# Input.net
KiCad netlist of a schematic drawn in Altium Designer
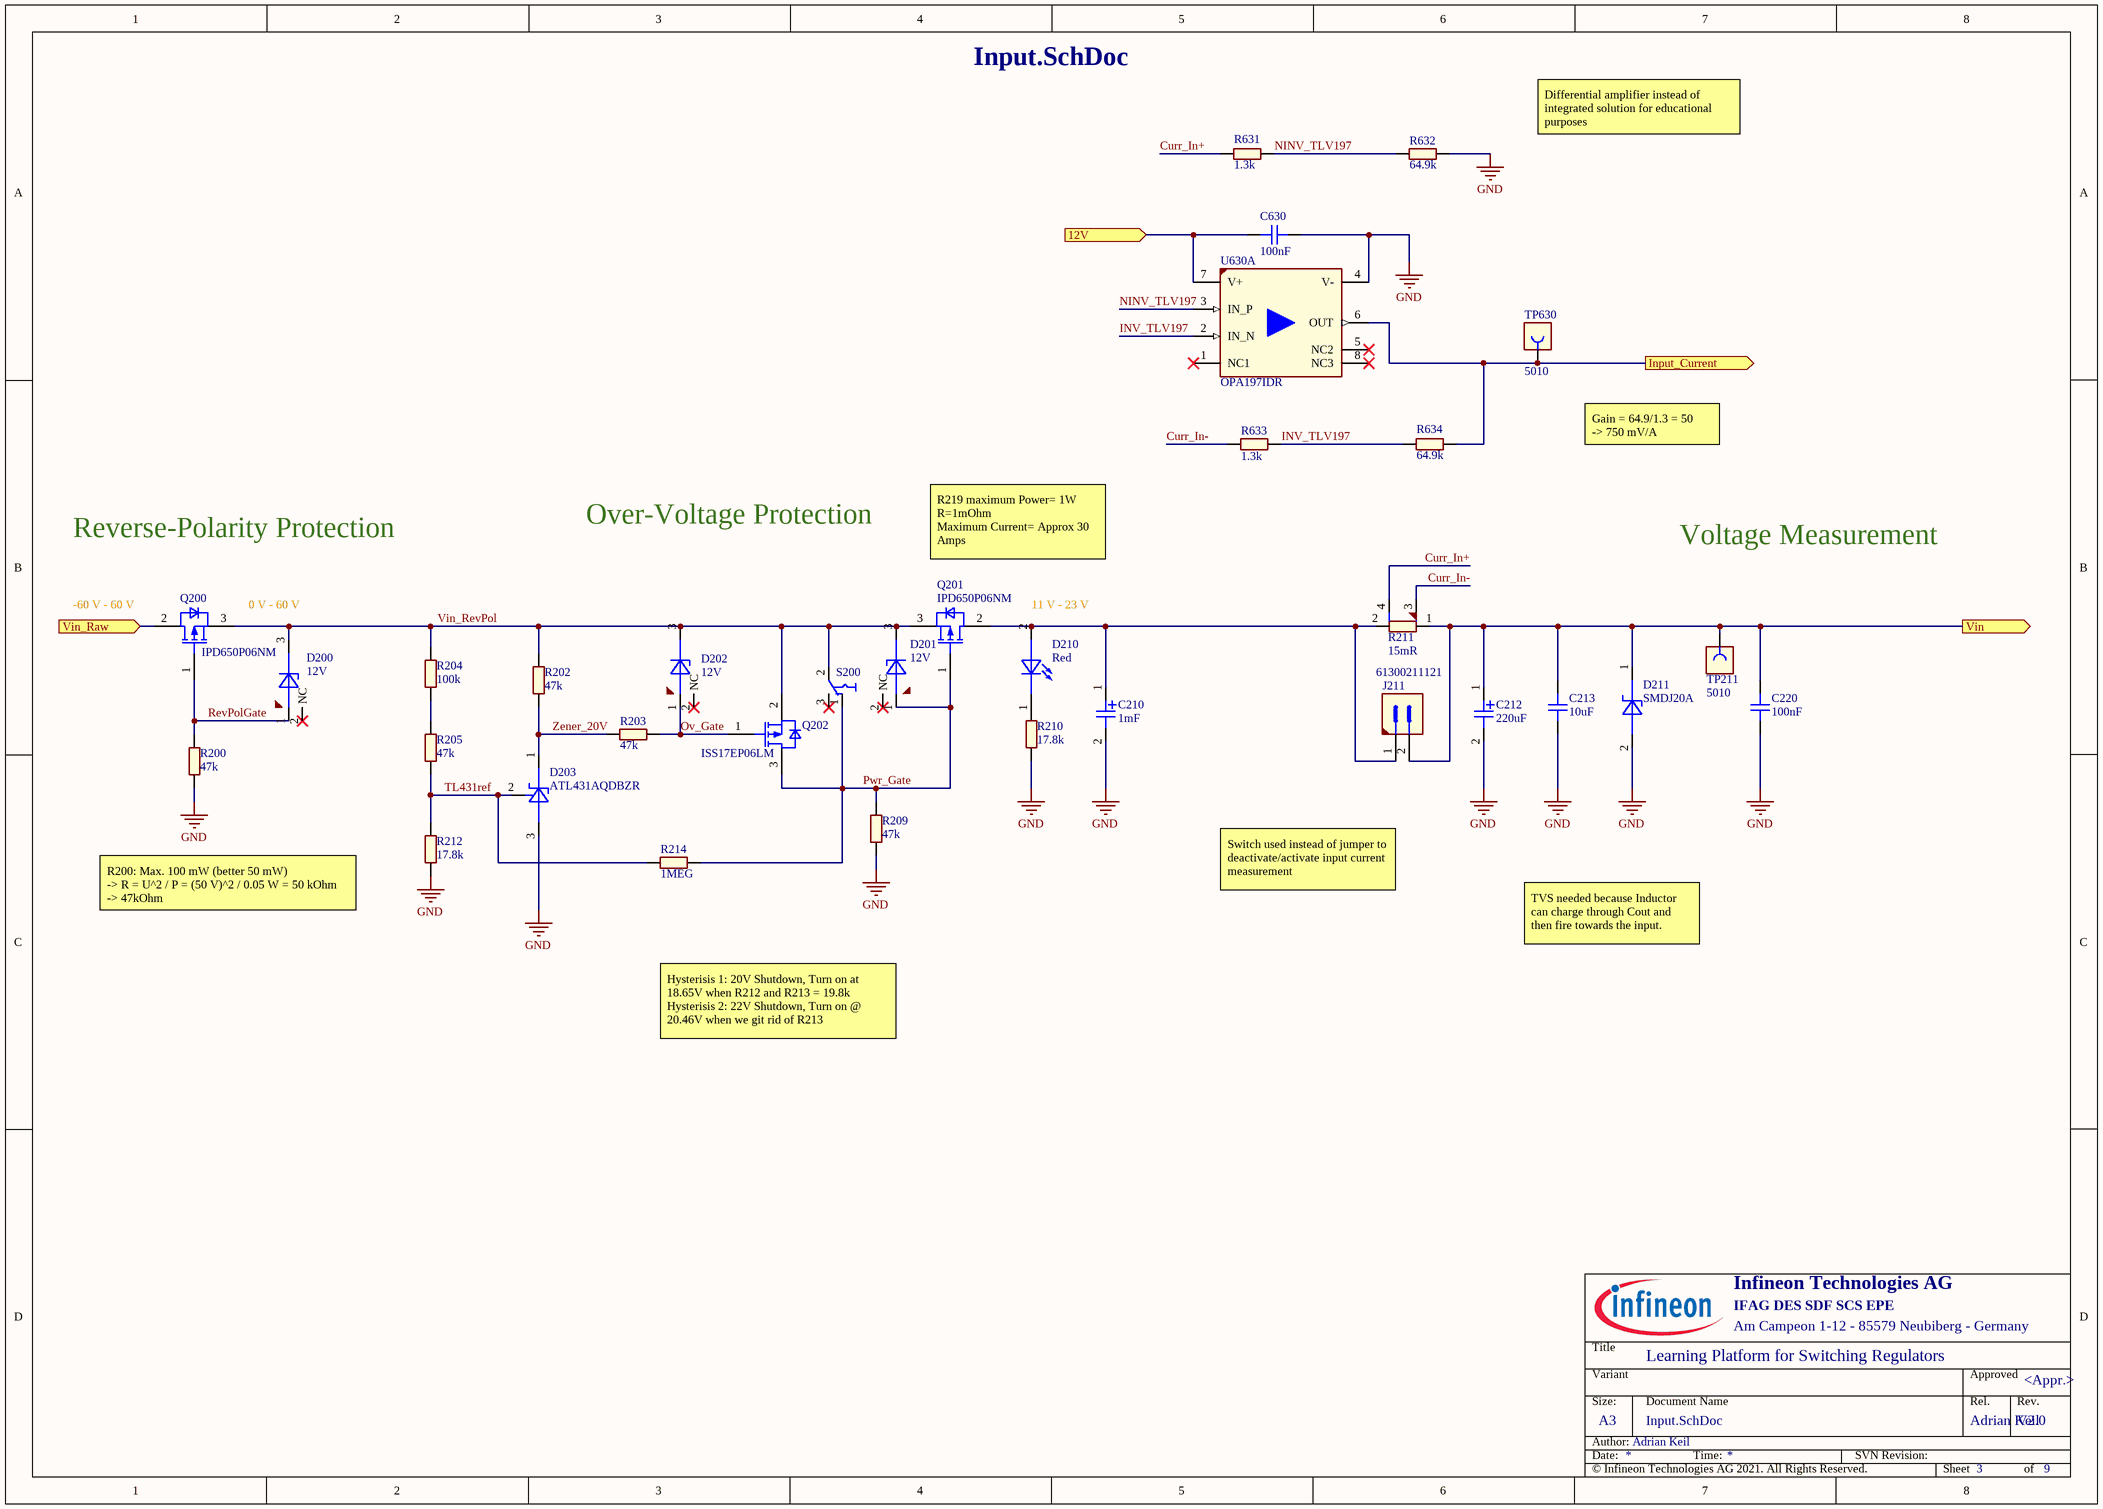
[diagram p0: Input.SchDoc]

(export (version "E")
  (design (tool "Eeschema 10.0.6"))
  (components
    (comp (ref "C210")
      (value "1mF")
      (footprint "CAPPRD500W60D1300H2700B")
      (fields (field (name "MANUFACTURER") "Kemet"))
      (libsource (lib "PCBLibraryData") (part "CAP-SGL-POL-02P_00000002"))
    )
    (comp (ref "C212")
      (value "220uF")
      (footprint "CAPAE1030X1050N-3")
      (fields (field (name "MANUFACTURER") "Nippon Chemi-Con"))
      (libsource (lib "PCBLibraryData") (part "CAP-SGL-POL-02P_00000002"))
    )
    (comp (ref "C213")
      (value "10uF")
      (footprint "CAPC3216X190N-1")
      (description "CAP / CERA / 10uF / 50V / 20% / X5R (EIA) / -55°C to 85°C / 1206 (3216) / SMD / -")
      (fields (field (name "MANUFACTURER") "Taiyo Yuden"))
      (libsource (lib "PCBLibraryData") (part "CAP-SGL-STD-02P_00000001"))
    )
    (comp (ref "C220")
      (value "100nF")
      (footprint "CAPC3216X125N-0")
      (description "CAP / CERA / 100nF / 50V / 10% / X7R (EIA) / -55°C to 125°C / 1206(3216) / SMD / -")
      (fields (field (name "LEGACY PARTNUMBER") "CAP01005660") (field (name "MANUFACTURER") "MuRata"))
      (libsource (lib "PCBLibraryData") (part "CAP-SGL-STD-02P_00000001"))
    )
    (comp (ref "C630")
      (value "100nF")
      (footprint "CAPC3216X125N-0")
      (description "CAP / CERA / 100nF / 50V / 10% / X7R (EIA) / -55°C to 125°C / 1206(3216) / SMD / -")
      (fields (field (name "LEGACY PARTNUMBER") "CAP01005660") (field (name "MANUFACTURER") "MuRata"))
      (libsource (lib "PCBLibraryData") (part "CAP-SGL-STD-02P_00000001"))
    )
    (comp (ref "D200")
      (value "12V")
      (footprint "SOT95P230X110-3N")
      (description "Voltage regulator diodes")
      (fields (field (name "MANUFACTURER") "Nexperia"))
      (libsource (lib "PCBLibraryData") (part "d_zener_a1c3_3p"))
    )
    (comp (ref "D201")
      (value "12V")
      (footprint "SOT95P230X110-3N")
      (description "Voltage regulator diodes")
      (fields (field (name "MANUFACTURER") "Nexperia"))
      (libsource (lib "PCBLibraryData") (part "d_zener_a1c3_3p"))
    )
    (comp (ref "D202")
      (value "12V")
      (footprint "SOT95P230X110-3N")
      (description "Voltage regulator diodes")
      (fields (field (name "MANUFACTURER") "Nexperia"))
      (libsource (lib "PCBLibraryData") (part "d_zener_a1c3_3p"))
    )
    (comp (ref "D203")
      (value "ATL431AQDBZR")
      (footprint "SOT95P237X112-3N-1")
      (description "ATL431 Adjustable Precision Shunt Regulator")
      (fields (field (name "MANUFACTURER") "Texas Instruments"))
      (libsource (lib "PCBLibraryData") (part "d_tvs_c1a3_3p"))
    )
    (comp (ref "D210")
      (value "Red")
      (footprint "LEDSC160X80X80-2N-1")
      (description "WL-SMCW SMT Mono-color Chip LED Waterclear, Red,630nm")
      (fields (field (name "MANUFACTURER") "Wurth Elektronik"))
      (libsource (lib "PCBLibraryData") (part "d_led_a"))
    )
    (comp (ref "D211")
      (value "SMDJ20A")
      (footprint "DIOM7959X262N")
      (description "TVS Diode, Low Profile Package, Built in Strain Relief, Glass Passivated Chip Junction")
      (fields (field (name "MANUFACTURER") "Littelfuse"))
      (libsource (lib "PCBLibraryData") (part "d_tvs_a"))
    )
    (comp (ref "J211")
      (value "61300211121")
      (footprint "CON-M-THT-61300211121")
      (description "Header, 2.54mm Pitch, 2 pin, Vertical, Single Row")
      (fields
        (field (name "LEGACY PARTNUMBER") "CON01500943")
        (field (name "MANUFACTURER") "Wurth Elektronik")
      )
      (libsource (lib "PCBLibraryData") (part "Header 2"))
    )
    (comp (ref "Q200")
      (value "IPD650P06NM")
      (footprint "TO228P998X250-3N-V2")
      (description "OptiMOS Power Transistor, -60 V")
      (fields (field (name "MANUFACTURER") "Infineon Technologies"))
      (libsource (lib "PCBLibraryData") (part "igfet_p_ch_enh_dio_1g2d3s_3p"))
    )
    (comp (ref "Q201")
      (value "IPD650P06NM")
      (footprint "TO228P998X250-3N-V2")
      (description "OptiMOS Power Transistor, -60 V")
      (fields (field (name "MANUFACTURER") "Infineon Technologies"))
      (libsource (lib "PCBLibraryData") (part "igfet_p_ch_enh_dio_1g2d3s_3p"))
    )
    (comp (ref "Q202")
      (value "ISS17EP06LM")
      (footprint "SOT95P240X110-3N-1-V")
      (description "OptiMOSTM Small Signal Transistor, -60 V")
      (fields (field (name "MANUFACTURER") "Infineon Technologies"))
      (libsource (lib "PCBLibraryData") (part "igfet_p_ch_enh_dio_1g2s3d_3p"))
    )
    (comp (ref "R200")
      (value "47k")
      (footprint "RESC3216X60N")
      (description "RES / STD / 47k / 250mW / 1% / 100ppm/K / -55°C to 155°C / 1206(3216) / SMD / -")
      (fields (field (name "LEGACY PARTNUMBER") "RES01802933") (field (name "MANUFACTURER") "Vishay"))
      (libsource (lib "") (part "RES-SGL-STD-02P_00000006_2"))
    )
    (comp (ref "R202")
      (value "47k")
      (footprint "RESC3216X60N")
      (description "RES / STD / 47k / 250mW / 1% / 100ppm/K / -55°C to 155°C / 1206(3216) / SMD / -")
      (fields (field (name "LEGACY PARTNUMBER") "RES01802933") (field (name "MANUFACTURER") "Vishay"))
      (libsource (lib "") (part "RES-SGL-STD-02P_00000006_2"))
    )
    (comp (ref "R203")
      (value "47k")
      (footprint "RESC3216X60N")
      (description "RES / STD / 47k / 250mW / 1% / 100ppm/K / -55°C to 155°C / 1206(3216) / SMD / -")
      (fields (field (name "LEGACY PARTNUMBER") "RES01802933") (field (name "MANUFACTURER") "Vishay"))
      (libsource (lib "") (part "RES-SGL-STD-02P_00000006_3"))
    )
    (comp (ref "R204")
      (value "100k")
      (footprint "RESC3216X60N")
      (description "RES / STD / 100k / 250mW / 1% / 100ppm/K / -55°C to 155°C / 1206(3216) / SMD / -")
      (fields (field (name "LEGACY PARTNUMBER") "RES01802971") (field (name "MANUFACTURER") "Vishay"))
      (libsource (lib "PCBLibraryData") (part "RES-SGL-STD-02P_00000006"))
    )
    (comp (ref "R205")
      (value "47k")
      (footprint "RESC3216X60N")
      (description "RES / STD / 47k / 250mW / 1% / 100ppm/K / -55°C to 155°C / 1206(3216) / SMD / -")
      (fields (field (name "LEGACY PARTNUMBER") "RES01802933") (field (name "MANUFACTURER") "Vishay"))
      (libsource (lib "") (part "RES-SGL-STD-02P_00000006_2"))
    )
    (comp (ref "R209")
      (value "47k")
      (footprint "RESC3216X60N")
      (description "RES / STD / 47k / 250mW / 1% / 100ppm/K / -55°C to 155°C / 1206(3216) / SMD / -")
      (fields (field (name "LEGACY PARTNUMBER") "RES01802933") (field (name "MANUFACTURER") "Vishay"))
      (libsource (lib "") (part "RES-SGL-STD-02P_00000006_2"))
    )
    (comp (ref "R210")
      (value "17.8k")
      (footprint "RESC3216X60N")
      (description "RES / STD / 17.8k / 250mW / 1% / 100ppm/K / -55°C to 155°C / 1206(3216) / SMD / -")
      (fields (field (name "LEGACY PARTNUMBER") "RES01802883") (field (name "MANUFACTURER") "Vishay"))
      (libsource (lib "PCBLibraryData") (part "RES-SGL-STD-02P_00000006"))
    )
    (comp (ref "R211")
      (value "15mR")
      (footprint "RES-SMD-L4T12")
      (description "RES / STD / 15mR / 500mW / 1% / 75ppm/K / -55°C to 155°C / 1206 (3216) / SMD / -")
      (fields (field (name "MANUFACTURER") "Ohmite"))
      (libsource (lib "PCBLibraryData") (part "RES-SHT-STD-04P_00097BE5"))
    )
    (comp (ref "R212")
      (value "17.8k")
      (footprint "RESC3216X60N")
      (description "RES / STD / 17.8k / 250mW / 1% / 100ppm/K / -55°C to 155°C / 1206(3216) / SMD / -")
      (fields (field (name "LEGACY PARTNUMBER") "RES01802883") (field (name "MANUFACTURER") "Vishay"))
      (libsource (lib "PCBLibraryData") (part "RES-SGL-STD-02P_00000006"))
    )
    (comp (ref "R214")
      (value "1MEG")
      (footprint "RESC3216X60N")
      (description "RES / STD / 1MEG / 250mW / 1% / 100ppm/K / -55°C to 155°C / 1206(3216) / SMD / -")
      (fields (field (name "LEGACY PARTNUMBER") "RES01803085") (field (name "MANUFACTURER") "Vishay"))
      (libsource (lib "") (part "RES-SGL-STD-02P_00000006_1"))
    )
    (comp (ref "R631")
      (value "1.3k")
      (footprint "RESC3216X60N")
      (description "RES / STD / 1.3k / 250mW / 1% / 100ppm/K / -55°C to 155°C / 1206(3216) / SMD / -")
      (fields (field (name "LEGACY PARTNUMBER") "RES01802755") (field (name "MANUFACTURER") "Vishay"))
      (libsource (lib "") (part "RES-SGL-STD-02P_00000006_1"))
    )
    (comp (ref "R632")
      (value "64.9k")
      (footprint "RESC3216X60N")
      (description "RES / STD / 64.9k / 250mW / 1% / 100ppm/K / -55°C to 155°C / 1206(3216) / SMD / -")
      (fields (field (name "LEGACY PARTNUMBER") "RES01802950") (field (name "MANUFACTURER") "Vishay"))
      (libsource (lib "") (part "RES-SGL-STD-02P_00000006_1"))
    )
    (comp (ref "R633")
      (value "1.3k")
      (footprint "RESC3216X60N")
      (description "RES / STD / 1.3k / 250mW / 1% / 100ppm/K / -55°C to 155°C / 1206(3216) / SMD / -")
      (fields (field (name "LEGACY PARTNUMBER") "RES01802755") (field (name "MANUFACTURER") "Vishay"))
      (libsource (lib "") (part "RES-SGL-STD-02P_00000006_1"))
    )
    (comp (ref "R634")
      (value "64.9k")
      (footprint "RESC3216X60N")
      (description "RES / STD / 64.9k / 250mW / 1% / 100ppm/K / -55°C to 155°C / 1206(3216) / SMD / -")
      (fields (field (name "LEGACY PARTNUMBER") "RES01802950") (field (name "MANUFACTURER") "Vishay"))
      (libsource (lib "") (part "RES-SGL-STD-02P_00000006_1"))
    )
    (comp (ref "S200")
      (value "CL-SB-12A-01T")
      (footprint "SW-SMD-CL-SB-12A-01T")
      (description "Slid Switch, 12V, 200mA")
      (fields (field (name "MANUFACTURER") "NIDEC COPAL ELECTRONICS, Inc."))
      (libsource (lib "PCBLibraryData") (part "sw_co213_3p"))
    )
    (comp (ref "TP211")
      (value "5010")
      (footprint "CON-THT-TP-5010")
      (description "PC Test Point-Multipurpose THT, Red")
      (fields
        (field (name "LEGACY PARTNUMBER") "CON01500529")
        (field (name "MANUFACTURER") "Keystone Electronics Corp.")
      )
      (libsource (lib "PCBLibraryData") (part "connector_1_f"))
    )
    (comp (ref "TP630")
      (value "5010")
      (footprint "CON-THT-TP-5010")
      (description "PC Test Point-Multipurpose THT, Red")
      (fields
        (field (name "LEGACY PARTNUMBER") "CON01500529")
        (field (name "MANUFACTURER") "Keystone Electronics Corp.")
      )
      (libsource (lib "") (part "connector_1_f_1"))
    )
    (comp (ref "U630")
      (value "OPA197IDR")
      (footprint "SOIC127P600X175-8N-23")
      (fields (field (name "MANUFACTURER") "Texas Instruments"))
      (libsource (lib "PCBLibraryData") (part "OPA140AID"))
    )
  )
  (nets
    (net (code "1") (name "/12V") (class "Default")
      (node (ref "C630") (pin "2") (pinfunction "2_2") (pintype "passive"))
      (node (ref "U630") (pin "7") (pinfunction "V+_7") (pintype "power_in"))
    )
    (net (code "2") (name "/Curr_In+") (class "Default")
      (node (ref "R211") (pin "4") (pinfunction "I2_4") (pintype "passive"))
      (node (ref "R631") (pin "1") (pinfunction "1_1") (pintype "passive"))
    )
    (net (code "3") (name "/Curr_In-") (class "Default")
      (node (ref "R211") (pin "3") (pinfunction "I1_3") (pintype "passive"))
      (node (ref "R633") (pin "1") (pinfunction "1_1") (pintype "passive"))
    )
    (net (code "4") (name "/INV_TLV197") (class "Default")
      (node (ref "R633") (pin "2") (pinfunction "2_2") (pintype "passive"))
      (node (ref "R634") (pin "1") (pinfunction "1_1") (pintype "passive"))
      (node (ref "U630") (pin "2") (pinfunction "IN_N_2") (pintype "input"))
    )
    (net (code "5") (name "/Input_Current") (class "Default")
      (node (ref "R634") (pin "2") (pinfunction "2_2") (pintype "passive"))
      (node (ref "TP630") (pin "1") (pinfunction "1_1") (pintype "passive"))
      (node (ref "U630") (pin "6") (pinfunction "OUT_6") (pintype "output"))
    )
    (net (code "6") (name "/NINV_TLV197") (class "Default")
      (node (ref "R631") (pin "2") (pinfunction "2_2") (pintype "passive"))
      (node (ref "R632") (pin "1") (pinfunction "1_1") (pintype "passive"))
      (node (ref "U630") (pin "3") (pinfunction "IN_P_3") (pintype "input"))
    )
    (net (code "7") (name "/Ov_Gate") (class "Default")
      (node (ref "D202") (pin "1") (pinfunction "ANODE_1") (pintype "passive"))
      (node (ref "Q202") (pin "1") (pinfunction "GATE_1") (pintype "passive"))
      (node (ref "R203") (pin "1") (pinfunction "1_1") (pintype "passive"))
    )
    (net (code "8") (name "/Pwr_Gate") (class "Default")
      (node (ref "D201") (pin "1") (pinfunction "ANODE_1") (pintype "passive"))
      (node (ref "Q201") (pin "1") (pinfunction "GATE_1") (pintype "passive"))
      (node (ref "Q202") (pin "3") (pinfunction "DRAIN_3") (pintype "passive"))
      (node (ref "R209") (pin "2") (pinfunction "2_2") (pintype "passive"))
      (node (ref "R214") (pin "2") (pinfunction "2_2") (pintype "passive"))
      (node (ref "S200") (pin "1") (pinfunction "1_1") (pintype "passive"))
    )
    (net (code "9") (name "/RevPolGate") (class "Default")
      (node (ref "D200") (pin "1") (pinfunction "ANODE_1") (pintype "passive"))
      (node (ref "Q200") (pin "1") (pinfunction "GATE_1") (pintype "passive"))
      (node (ref "R200") (pin "2") (pinfunction "2_2") (pintype "passive"))
    )
    (net (code "10") (name "/TL431ref") (class "Default")
      (node (ref "D203") (pin "2") (pinfunction "REF_2") (pintype "passive"))
      (node (ref "R205") (pin "1") (pinfunction "1_1") (pintype "passive"))
      (node (ref "R212") (pin "1") (pinfunction "1_1") (pintype "passive"))
      (node (ref "R214") (pin "1") (pinfunction "1_1") (pintype "passive"))
    )
    (net (code "11") (name "/Vin") (class "Default")
      (node (ref "C212") (pin "1") (pinfunction "1_1") (pintype "passive"))
      (node (ref "C213") (pin "2") (pinfunction "2_2") (pintype "passive"))
      (node (ref "C220") (pin "1") (pinfunction "1_1") (pintype "passive"))
      (node (ref "D211") (pin "1") (pinfunction "CATHODE_1") (pintype "passive"))
      (node (ref "J211") (pin "2") (pinfunction "2_2") (pintype "passive"))
      (node (ref "R211") (pin "1") (pinfunction "V1_1") (pintype "passive"))
      (node (ref "TP211") (pin "1") (pinfunction "1_1") (pintype "passive"))
    )
    (net (code "12") (name "/Vin_Raw") (class "Default")
      (node (ref "Q200") (pin "2") (pinfunction "DRAIN_2") (pintype "passive"))
    )
    (net (code "13") (name "/Vin_RevPol") (class "Default")
      (node (ref "D200") (pin "3") (pinfunction "CATHODE_3") (pintype "passive"))
      (node (ref "D201") (pin "3") (pinfunction "CATHODE_3") (pintype "passive"))
      (node (ref "D202") (pin "3") (pinfunction "CATHODE_3") (pintype "passive"))
      (node (ref "Q200") (pin "3") (pinfunction "SOURCE_3") (pintype "passive"))
      (node (ref "Q201") (pin "3") (pinfunction "SOURCE_3") (pintype "passive"))
      (node (ref "Q202") (pin "2") (pinfunction "SOURCE_2") (pintype "passive"))
      (node (ref "R202") (pin "2") (pinfunction "2_2") (pintype "passive"))
      (node (ref "R204") (pin "1") (pinfunction "1_1") (pintype "passive"))
      (node (ref "S200") (pin "2") (pinfunction "2_2") (pintype "passive"))
    )
    (net (code "14") (name "/Zener_20V") (class "Default")
      (node (ref "D203") (pin "1") (pinfunction "CATHODE_1") (pintype "passive"))
      (node (ref "R202") (pin "1") (pinfunction "1_1") (pintype "passive"))
      (node (ref "R203") (pin "2") (pinfunction "2_2") (pintype "passive"))
    )
    (net (code "15") (name "GND") (class "Default")
      (node (ref "C210") (pin "2") (pinfunction "2_2") (pintype "passive"))
      (node (ref "C212") (pin "2") (pinfunction "2_2") (pintype "passive"))
      (node (ref "C213") (pin "1") (pinfunction "1_1") (pintype "passive"))
      (node (ref "C220") (pin "2") (pinfunction "2_2") (pintype "passive"))
      (node (ref "C630") (pin "1") (pinfunction "1_1") (pintype "passive"))
      (node (ref "D203") (pin "3") (pinfunction "ANODE_3") (pintype "passive"))
      (node (ref "D211") (pin "2") (pinfunction "ANODE_2") (pintype "passive"))
      (node (ref "R200") (pin "1") (pinfunction "1_1") (pintype "passive"))
      (node (ref "R209") (pin "1") (pinfunction "1_1") (pintype "passive"))
      (node (ref "R210") (pin "2") (pinfunction "2_2") (pintype "passive"))
      (node (ref "R212") (pin "2") (pinfunction "2_2") (pintype "passive"))
      (node (ref "R632") (pin "2") (pinfunction "2_2") (pintype "passive"))
      (node (ref "U630") (pin "4") (pinfunction "V-_4") (pintype "power_in"))
    )
    (net (code "16") (name "Net-(D210-Anode)") (class "Default")
      (node (ref "C210") (pin "1") (pinfunction "1_1") (pintype "passive"))
      (node (ref "D210") (pin "2") (pinfunction "Anode_2") (pintype "passive"))
      (node (ref "J211") (pin "1") (pinfunction "1_1") (pintype "passive"))
      (node (ref "Q201") (pin "2") (pinfunction "DRAIN_2") (pintype "passive"))
      (node (ref "R211") (pin "2") (pinfunction "V2_2") (pintype "passive"))
    )
    (net (code "17") (name "Net-(D210-Cathode)") (class "Default")
      (node (ref "D210") (pin "1") (pinfunction "Cathode_1") (pintype "passive"))
      (node (ref "R210") (pin "1") (pinfunction "1_1") (pintype "passive"))
    )
    (net (code "18") (name "Net-(R204-Pad2)") (class "Default")
      (node (ref "R204") (pin "2") (pinfunction "2_2") (pintype "passive"))
      (node (ref "R205") (pin "2") (pinfunction "2_2") (pintype "passive"))
    )
    (net (code "19") (name "unconnected-(D200-NC-Pad2)") (class "Default")
      (node (ref "D200") (pin "2") (pinfunction "NC_2") (pintype "passive+no_connect"))
    )
    (net (code "20") (name "unconnected-(D201-NC-Pad2)") (class "Default")
      (node (ref "D201") (pin "2") (pinfunction "NC_2") (pintype "passive+no_connect"))
    )
    (net (code "21") (name "unconnected-(D202-NC-Pad2)") (class "Default")
      (node (ref "D202") (pin "2") (pinfunction "NC_2") (pintype "passive+no_connect"))
    )
    (net (code "22") (name "unconnected-(S200-Pad3)") (class "Default")
      (node (ref "S200") (pin "3") (pinfunction "3_3") (pintype "passive+no_connect"))
    )
    (net (code "23") (name "unconnected-(U630-NC1-Pad1)") (class "Default")
      (node (ref "U630") (pin "1") (pinfunction "NC1_1") (pintype "passive+no_connect"))
    )
    (net (code "24") (name "unconnected-(U630-NC2-Pad5)") (class "Default")
      (node (ref "U630") (pin "5") (pinfunction "NC2_5") (pintype "passive+no_connect"))
    )
    (net (code "25") (name "unconnected-(U630-NC3-Pad8)") (class "Default")
      (node (ref "U630") (pin "8") (pinfunction "NC3_8") (pintype "passive+no_connect"))
    )
  )
)
